# Power_Supply_No_Slo_Start-Cameron.net
KiCad netlist of a schematic drawn in EAGLE
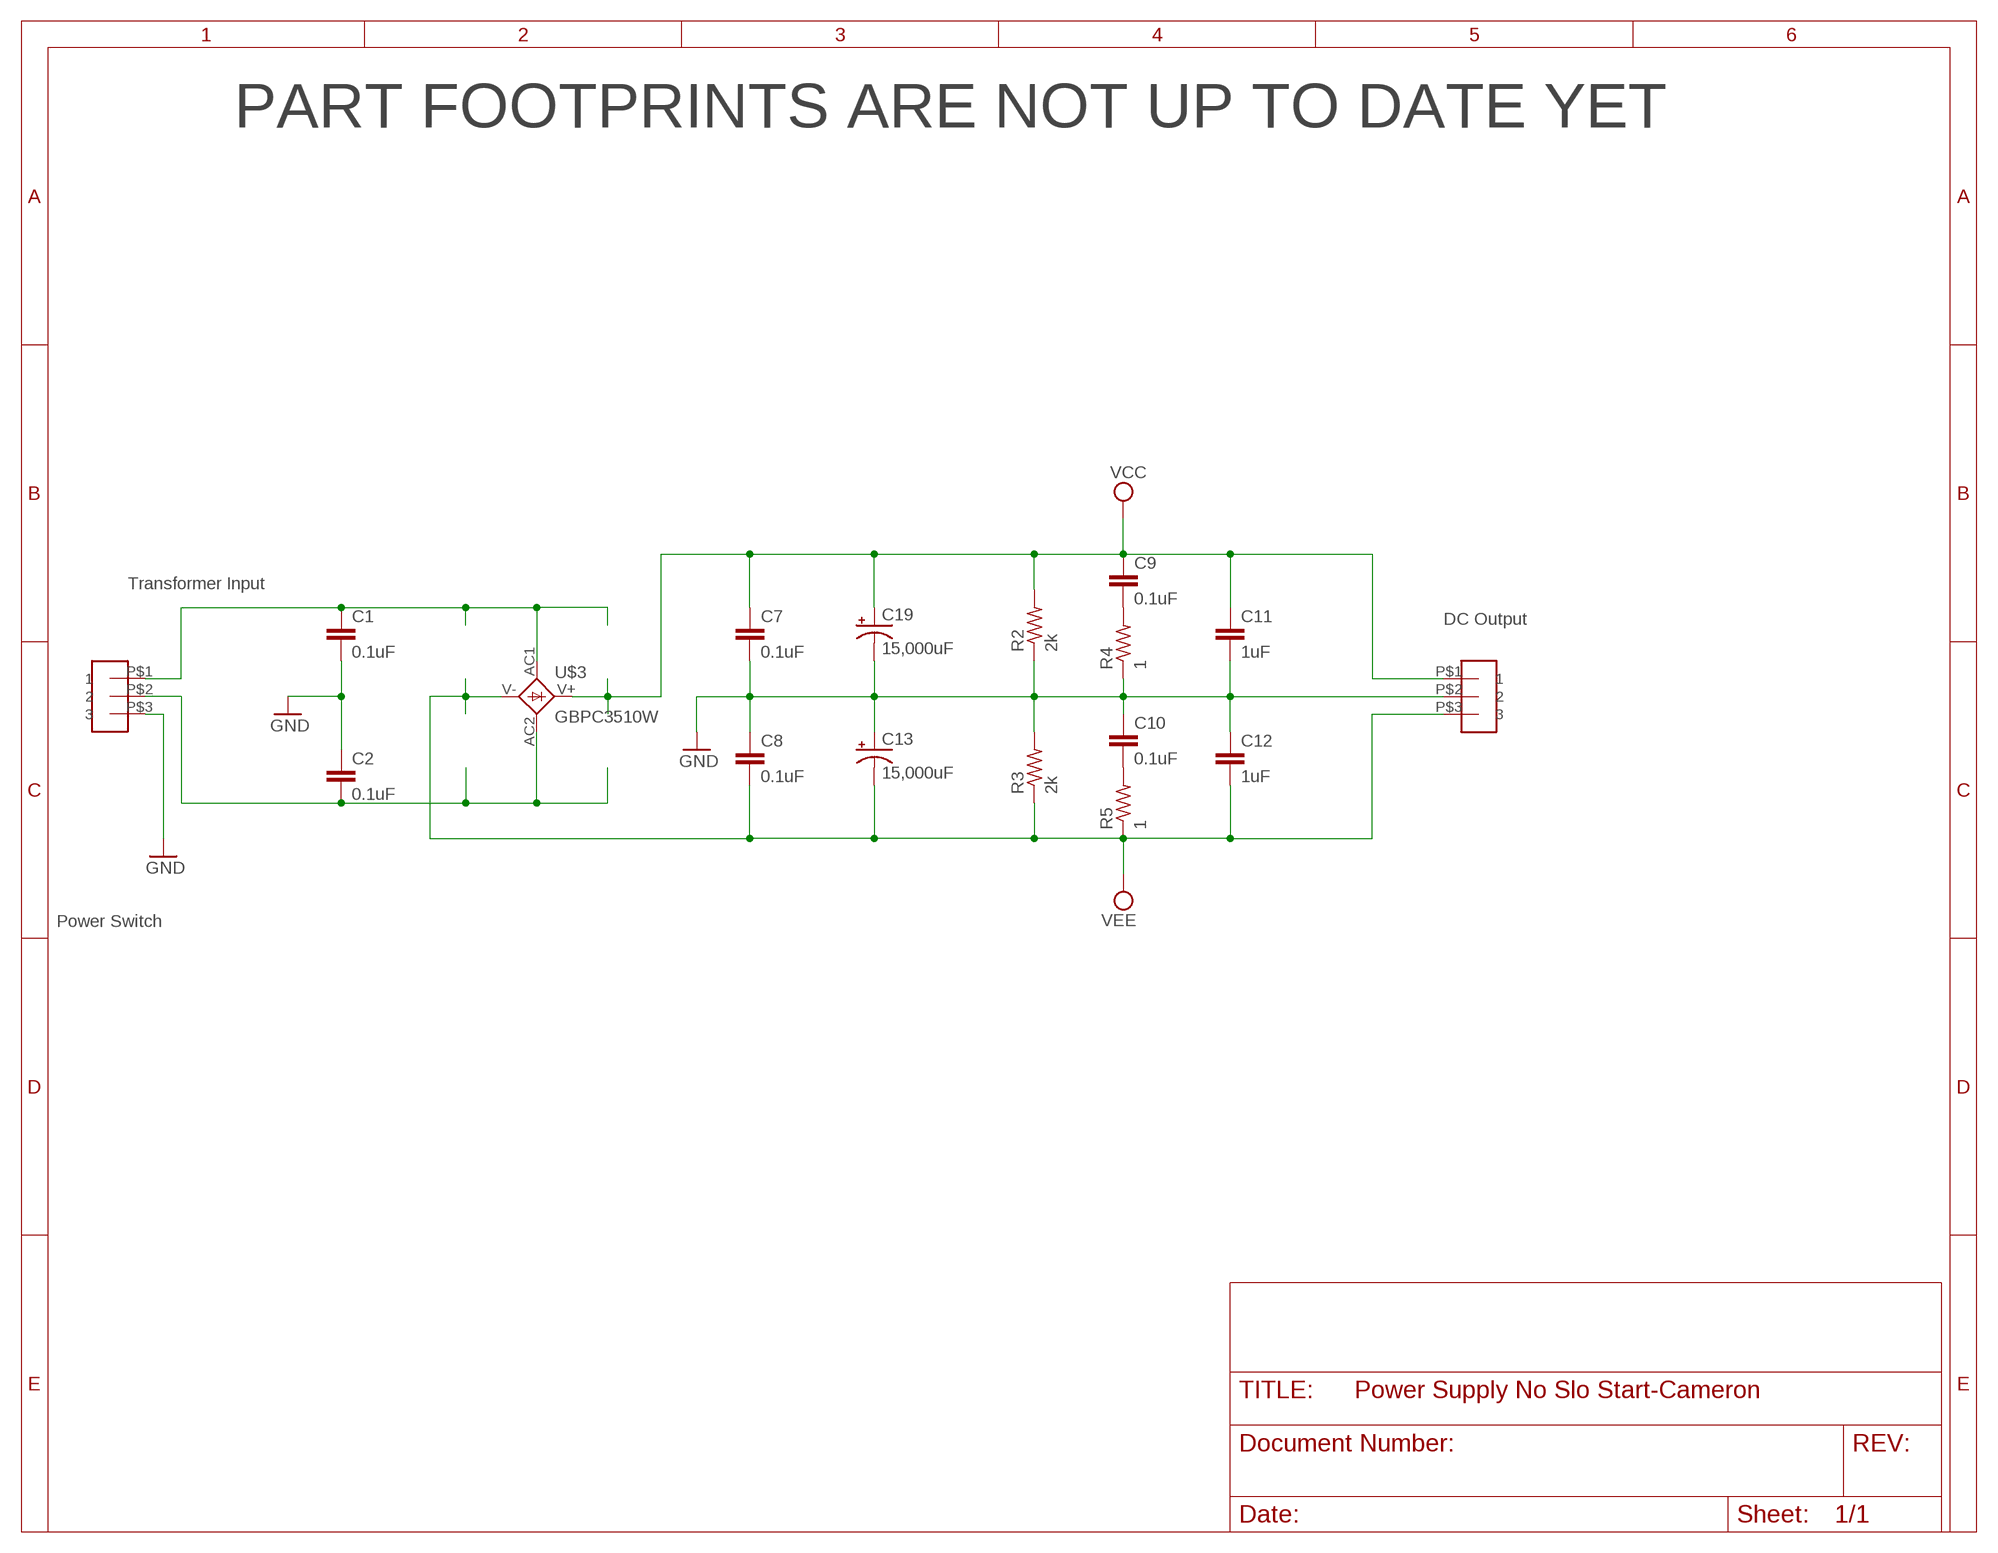
[diagram p0: schematic, sheet 1]

(export (version "E")
  (design (tool "Eeschema 10.0.6"))
  (components
    (comp (ref "C1")
      (value "0.1uF")
      (footprint "eagle-import:C102-064X133")
      (libsource (lib "eagle-import") (part "C-EU102-064X133"))
    )
    (comp (ref "C2")
      (value "0.1uF")
      (footprint "eagle-import:C102-064X133")
      (libsource (lib "eagle-import") (part "C-EU102-064X133"))
    )
    (comp (ref "C7")
      (value "0.1uF")
      (footprint "eagle-import:C102-064X133")
      (libsource (lib "eagle-import") (part "C-EU102-064X133"))
    )
    (comp (ref "C8")
      (value "0.1uF")
      (footprint "eagle-import:C102-064X133")
      (libsource (lib "eagle-import") (part "C-EU102-064X133"))
    )
    (comp (ref "C9")
      (value "0.1uF")
      (footprint "eagle-import:C102-064X133")
      (libsource (lib "eagle-import") (part "C-EU102-064X133"))
    )
    (comp (ref "C10")
      (value "0.1uF")
      (footprint "eagle-import:C102-064X133")
      (libsource (lib "eagle-import") (part "C-EU102-064X133"))
    )
    (comp (ref "C11")
      (value "1uF")
      (footprint "eagle-import:C102-064X133")
      (libsource (lib "eagle-import") (part "C-EU102-064X133"))
    )
    (comp (ref "C12")
      (value "1uF")
      (footprint "eagle-import:C102-064X133")
      (libsource (lib "eagle-import") (part "C-EU102-064X133"))
    )
    (comp (ref "C13")
      (value "15,000uF")
      (footprint "eagle-import:PHI-35")
      (libsource (lib "eagle-import") (part "LNR1K153MSE"))
    )
    (comp (ref "C19")
      (value "15,000uF")
      (footprint "eagle-import:PHI-35")
      (libsource (lib "eagle-import") (part "LNR1K153MSE"))
    )
    (comp (ref "P1")
      (value "3PIN_3.25MM")
      (footprint "eagle-import:3PIN_SCREW_EYELET")
      (libsource (lib "eagle-import") (part "3PIN_3.25MM"))
    )
    (comp (ref "P2")
      (value "3PIN_3.25MM")
      (footprint "eagle-import:3PIN_SCREW_EYELET")
      (libsource (lib "eagle-import") (part "3PIN_3.25MM"))
    )
    (comp (ref "R2")
      (value "2k")
      (footprint "eagle-import:VTA52")
      (libsource (lib "eagle-import") (part "R-US_VTA52"))
    )
    (comp (ref "R3")
      (value "2k")
      (footprint "eagle-import:VTA52")
      (libsource (lib "eagle-import") (part "R-US_VTA52"))
    )
    (comp (ref "R4")
      (value "1")
      (footprint "eagle-import:0411_12")
      (libsource (lib "eagle-import") (part "R-US_0411/12"))
    )
    (comp (ref "R5")
      (value "1")
      (footprint "eagle-import:0411_12")
      (libsource (lib "eagle-import") (part "R-US_0411/12"))
    )
    (comp (ref "U$3")
      (value "GBPC3510W")
      (footprint "eagle-import:GBPC3510W")
      (libsource (lib "eagle-import") (part "GBPC3510W"))
    )
  )
  (nets
    (net (code "1") (name "GND") (class "Default")
      (node (ref "C1") (pin "2") (pinfunction "2_2") (pintype "passive"))
      (node (ref "C10") (pin "1") (pinfunction "1_1") (pintype "passive"))
      (node (ref "C11") (pin "2") (pinfunction "2_2") (pintype "passive"))
      (node (ref "C12") (pin "1") (pinfunction "1_1") (pintype "passive"))
      (node (ref "C13") (pin "+") (pinfunction "+_+") (pintype "passive"))
      (node (ref "C19") (pin "-") (pinfunction "-_-") (pintype "passive"))
      (node (ref "C2") (pin "1") (pinfunction "1_1") (pintype "passive"))
      (node (ref "C7") (pin "2") (pinfunction "2_2") (pintype "passive"))
      (node (ref "C8") (pin "1") (pinfunction "1_1") (pintype "passive"))
      (node (ref "P1") (pin "P$3") (pinfunction "3_P$3") (pintype "bidirectional"))
      (node (ref "P2") (pin "P$2") (pinfunction "2_P$2") (pintype "bidirectional"))
      (node (ref "R2") (pin "1") (pinfunction "1_1") (pintype "passive"))
      (node (ref "R3") (pin "2") (pinfunction "2_2") (pintype "passive"))
      (node (ref "R4") (pin "1") (pinfunction "1_1") (pintype "passive"))
    )
    (net (code "2") (name "Net-(C9-Pad2)") (class "Default")
      (node (ref "C9") (pin "2") (pinfunction "2_2") (pintype "passive"))
      (node (ref "R4") (pin "2") (pinfunction "2_2") (pintype "passive"))
    )
    (net (code "3") (name "Net-(C10-Pad2)") (class "Default")
      (node (ref "C10") (pin "2") (pinfunction "2_2") (pintype "passive"))
      (node (ref "R5") (pin "2") (pinfunction "2_2") (pintype "passive"))
    )
    (net (code "4") (name "Net-(P1-1)") (class "Default")
      (node (ref "C1") (pin "1") (pinfunction "1_1") (pintype "passive"))
      (node (ref "P1") (pin "P$1") (pinfunction "1_P$1") (pintype "bidirectional"))
      (node (ref "U$3") (pin "AC1") (pinfunction "AC1_AC1") (pintype "passive"))
    )
    (net (code "5") (name "Net-(P1-2)") (class "Default")
      (node (ref "C2") (pin "2") (pinfunction "2_2") (pintype "passive"))
      (node (ref "P1") (pin "P$2") (pinfunction "2_P$2") (pintype "bidirectional"))
      (node (ref "U$3") (pin "AC2") (pinfunction "AC2_AC2") (pintype "passive"))
    )
    (net (code "6") (name "VCC") (class "Default")
      (node (ref "C11") (pin "1") (pinfunction "1_1") (pintype "passive"))
      (node (ref "C19") (pin "+") (pinfunction "+_+") (pintype "passive"))
      (node (ref "C7") (pin "1") (pinfunction "1_1") (pintype "passive"))
      (node (ref "C9") (pin "1") (pinfunction "1_1") (pintype "passive"))
      (node (ref "P2") (pin "P$1") (pinfunction "1_P$1") (pintype "bidirectional"))
      (node (ref "R2") (pin "2") (pinfunction "2_2") (pintype "passive"))
      (node (ref "U$3") (pin "V+") (pinfunction "+_V+") (pintype "passive"))
    )
    (net (code "7") (name "VEE") (class "Default")
      (node (ref "C12") (pin "2") (pinfunction "2_2") (pintype "passive"))
      (node (ref "C13") (pin "-") (pinfunction "-_-") (pintype "passive"))
      (node (ref "C8") (pin "2") (pinfunction "2_2") (pintype "passive"))
      (node (ref "P2") (pin "P$3") (pinfunction "3_P$3") (pintype "bidirectional"))
      (node (ref "R3") (pin "1") (pinfunction "1_1") (pintype "passive"))
      (node (ref "R5") (pin "1") (pinfunction "1_1") (pintype "passive"))
      (node (ref "U$3") (pin "V-") (pinfunction "-_V-") (pintype "passive"))
    )
  )
)
